# micro.net
KiCad netlist of a schematic drawn in EAGLE
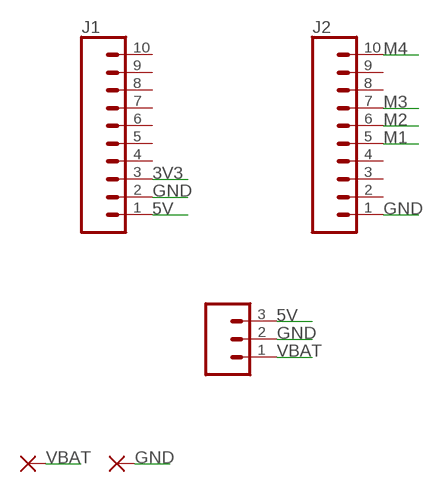
[diagram p0: schematic, sheet 1]

(export (version "E")
  (design (tool "Eeschema 10.0.6"))
  (components
    (comp (ref "J1")
      (value "CONN_10NO_SILK_PTH_FEMALE")
      (footprint "eagle-import:1X10_NO_SILK")
      (libsource (lib "eagle-import") (part "CONN_10NO_SILK_PTH_FEMALE"))
    )
    (comp (ref "J2")
      (value "CONN_10NO_SILK_PTH_FEMALE")
      (footprint "eagle-import:1X10_NO_SILK")
      (libsource (lib "eagle-import") (part "CONN_10NO_SILK_PTH_FEMALE"))
    )
    (comp (ref "J3")
      (value "CONN_031X03_NO_SILK")
      (footprint "eagle-import:1X03_NO_SILK")
      (libsource (lib "eagle-import") (part "CONN_031X03_NO_SILK"))
    )
    (comp (ref "PAD1")
      (value "SMD5")
      (footprint "eagle-import:SMD2,54-5,08")
      (libsource (lib "eagle-import") (part "SMD5"))
    )
    (comp (ref "PAD2")
      (value "SMD5")
      (footprint "eagle-import:SMD2,54-5,08")
      (libsource (lib "eagle-import") (part "SMD5"))
    )
  )
  (nets
    (net (code "1") (name "/3V3") (class "Default")
      (node (ref "J1") (pin "3") (pinfunction "3_3") (pintype "passive"))
    )
    (net (code "2") (name "/5V") (class "Default")
      (node (ref "J1") (pin "1") (pinfunction "1_1") (pintype "passive"))
      (node (ref "J3") (pin "3") (pinfunction "3_3") (pintype "passive"))
    )
    (net (code "3") (name "/GND") (class "Default")
      (node (ref "J1") (pin "2") (pinfunction "2_2") (pintype "passive"))
      (node (ref "J2") (pin "1") (pinfunction "1_1") (pintype "passive"))
      (node (ref "J3") (pin "2") (pinfunction "2_2") (pintype "passive"))
      (node (ref "PAD2") (pin "1") (pinfunction "P_1") (pintype "passive"))
    )
    (net (code "4") (name "/M1") (class "Default")
      (node (ref "J2") (pin "5") (pinfunction "5_5") (pintype "passive"))
    )
    (net (code "5") (name "/M2") (class "Default")
      (node (ref "J2") (pin "6") (pinfunction "6_6") (pintype "passive"))
    )
    (net (code "6") (name "/M3") (class "Default")
      (node (ref "J2") (pin "7") (pinfunction "7_7") (pintype "passive"))
    )
    (net (code "7") (name "/M4") (class "Default")
      (node (ref "J2") (pin "10") (pinfunction "10_10") (pintype "passive"))
    )
    (net (code "8") (name "/VBAT") (class "Default")
      (node (ref "J3") (pin "1") (pinfunction "1_1") (pintype "passive"))
      (node (ref "PAD1") (pin "1") (pinfunction "P_1") (pintype "passive"))
    )
    (net (code "9") (name "unconnected-(J1-Pad4)") (class "Default")
      (node (ref "J1") (pin "4") (pinfunction "4_4") (pintype "passive"))
    )
    (net (code "10") (name "unconnected-(J1-Pad5)") (class "Default")
      (node (ref "J1") (pin "5") (pinfunction "5_5") (pintype "passive"))
    )
    (net (code "11") (name "unconnected-(J1-Pad6)") (class "Default")
      (node (ref "J1") (pin "6") (pinfunction "6_6") (pintype "passive"))
    )
    (net (code "12") (name "unconnected-(J1-Pad7)") (class "Default")
      (node (ref "J1") (pin "7") (pinfunction "7_7") (pintype "passive"))
    )
    (net (code "13") (name "unconnected-(J1-Pad8)") (class "Default")
      (node (ref "J1") (pin "8") (pinfunction "8_8") (pintype "passive"))
    )
    (net (code "14") (name "unconnected-(J1-Pad9)") (class "Default")
      (node (ref "J1") (pin "9") (pinfunction "9_9") (pintype "passive"))
    )
    (net (code "15") (name "unconnected-(J1-Pad10)") (class "Default")
      (node (ref "J1") (pin "10") (pinfunction "10_10") (pintype "passive"))
    )
    (net (code "16") (name "unconnected-(J2-Pad2)") (class "Default")
      (node (ref "J2") (pin "2") (pinfunction "2_2") (pintype "passive"))
    )
    (net (code "17") (name "unconnected-(J2-Pad3)") (class "Default")
      (node (ref "J2") (pin "3") (pinfunction "3_3") (pintype "passive"))
    )
    (net (code "18") (name "unconnected-(J2-Pad4)") (class "Default")
      (node (ref "J2") (pin "4") (pinfunction "4_4") (pintype "passive"))
    )
    (net (code "19") (name "unconnected-(J2-Pad8)") (class "Default")
      (node (ref "J2") (pin "8") (pinfunction "8_8") (pintype "passive"))
    )
    (net (code "20") (name "unconnected-(J2-Pad9)") (class "Default")
      (node (ref "J2") (pin "9") (pinfunction "9_9") (pintype "passive"))
    )
  )
)
